# Page1.net
KiCad netlist of a schematic drawn in Altium Designer
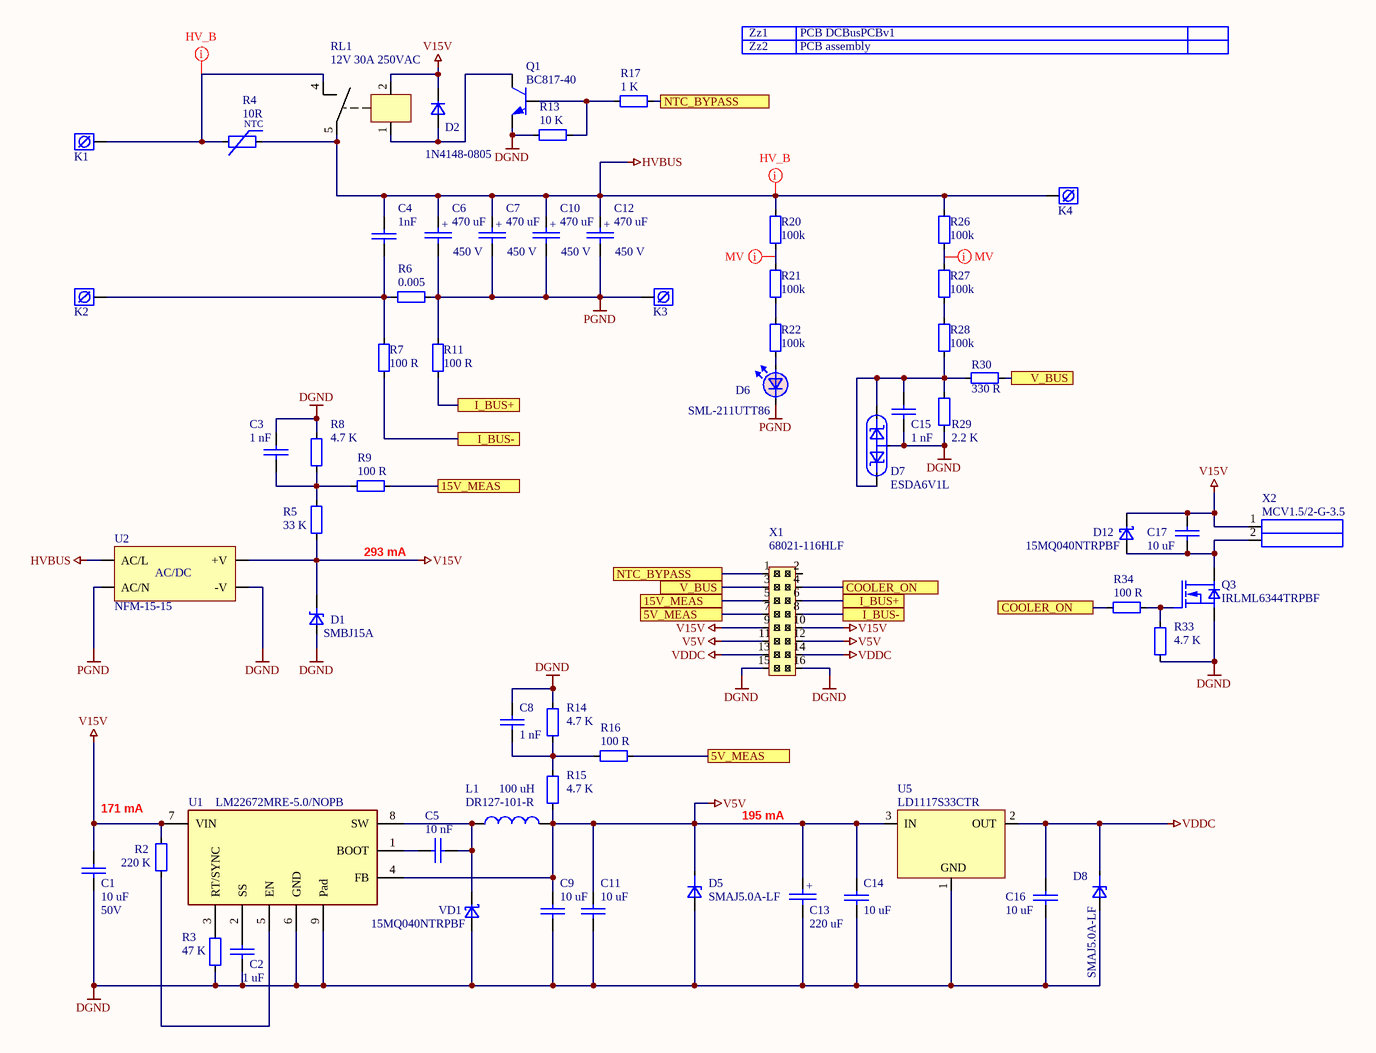
[diagram p0: Page1.SchDoc]

(export (version "E")
  (design (tool "Eeschema 10.0.6"))
  (components
    (comp (ref "C1")
      (value "10 uF")
      (footprint "3225[1210]")
      (description "10uF, 50V, 20%, Y5V (F), 1210")
      (fields
        (field (name "MANUFACTURER") "Murata Electronics North America")
        (field (name "TOLERANCE") "20%")
        (field (name "VOLTAGE") "50V")
      )
      (libsource (lib "ea_Capacitors") (part "GRM32DF51H106ZA01L"))
    )
    (comp (ref "C2")
      (value "1 uF")
      (footprint "2012[0805]")
      (description "1 uF, 10V, 10%, X7R, 0805")
      (fields (field (name "MANUFACTURER") "Murata") (field (name "TOLERANCE") "10%"))
      (libsource (lib "ea_Capacitors") (part "GRM21BR71A105KA01L"))
    )
    (comp (ref "C3")
      (value "1 nF")
      (footprint "1608[0603]")
      (description "1 nF, 50V, 10%, X7R, 0603 SMD MLC Capacitor")
      (fields (field (name "TOLERANCE") "10%") (field (name "MANUFACTURER") "SAMSUNG"))
      (libsource (lib "ea_Capacitors") (part "CVNF1.0K0603_1"))
    )
    (comp (ref "C4")
      (value "1nF")
      (footprint "B32529C8102J")
      (description "CAP FILM 1000PF 630VDC 400VAC RADIAL Lead Spacing 5mm")
      (fields (field (name "MANUFACTURER") "Epcos") (field (name "TOLERANCE") "20%"))
      (libsource (lib "ea_Capacitors") (part "B32529C8102J"))
    )
    (comp (ref "C5")
      (value "10 nF")
      (footprint "1608[0603]")
      (description "10 nF, 50V, 5%, X7R, 0603 SMD MLC Capacitor")
      (fields (field (name "TOLERANCE") "5%") (field (name "MANUFACTURER") "SAMSUNG"))
      (libsource (lib "ea_Capacitors") (part "CVNF010K0603"))
    )
    (comp (ref "C6")
      (value "470 uF")
      (footprint "ESMH451VNN471MA50T")
      (description "470uF 450V, 20%, -40..+85, 2000 Hrs @ 85°C, 35*50")
      (fields
        (field (name "MANUFACTURER") "UNITED CHEMICON")
        (field (name "TOLERANCE") "+-20%")
        (field (name "VOLTAGE") "450 V")
      )
      (libsource (lib "ea_Capacitors") (part "ESMH451VNN471MA50T"))
    )
    (comp (ref "C7")
      (value "470 uF")
      (footprint "ESMH451VNN471MA50T")
      (description "470uF 450V, 20%, -40..+85, 2000 Hrs @ 85°C, 35*50")
      (fields
        (field (name "MANUFACTURER") "UNITED CHEMICON")
        (field (name "TOLERANCE") "+-20%")
        (field (name "VOLTAGE") "450 V")
      )
      (libsource (lib "ea_Capacitors") (part "ESMH451VNN471MA50T"))
    )
    (comp (ref "C8")
      (value "1 nF")
      (footprint "1608[0603]")
      (description "1 nF, 50V, 10%, X7R, 0603 SMD MLC Capacitor")
      (fields (field (name "TOLERANCE") "10%") (field (name "MANUFACTURER") "SAMSUNG"))
      (libsource (lib "ea_Capacitors") (part "CVNF1.0K0603_1"))
    )
    (comp (ref "C9")
      (value "10 uF")
      (footprint "0805-1206")
      (description "CAP CER 10UF 10V 10% X5R 0805")
      (fields (field (name "MANUFACTURER") "Taiyo Yuden") (field (name "TOLERANCE") "10%"))
      (libsource (lib "ea_Capacitors") (part "LMK212F106ZG-T"))
    )
    (comp (ref "C10")
      (value "470 uF")
      (footprint "ESMH451VNN471MA50T")
      (description "470uF 450V, 20%, -40..+85, 2000 Hrs @ 85°C, 35*50")
      (fields
        (field (name "MANUFACTURER") "UNITED CHEMICON")
        (field (name "TOLERANCE") "+-20%")
        (field (name "VOLTAGE") "450 V")
      )
      (libsource (lib "ea_Capacitors") (part "ESMH451VNN471MA50T"))
    )
    (comp (ref "C11")
      (value "10 uF")
      (footprint "0805-1206")
      (description "CAP CER 10UF 10V 10% X5R 0805")
      (fields (field (name "MANUFACTURER") "Taiyo Yuden") (field (name "TOLERANCE") "10%"))
      (libsource (lib "ea_Capacitors") (part "LMK212F106ZG-T"))
    )
    (comp (ref "C12")
      (value "470 uF")
      (footprint "ESMH451VNN471MA50T")
      (description "470uF 450V, 20%, -40..+85, 2000 Hrs @ 85°C, 35*50")
      (fields
        (field (name "MANUFACTURER") "UNITED CHEMICON")
        (field (name "TOLERANCE") "+-20%")
        (field (name "VOLTAGE") "450 V")
      )
      (libsource (lib "ea_Capacitors") (part "ESMH451VNN471MA50T"))
    )
    (comp (ref "C13")
      (value "220 uF")
      (footprint "Tant case C (6032-28)")
      (description "220.0 uF, 10V 20%, -55...105 C, SMD Tantalum")
      (fields (field (name "MANUFACTURER") "AVX Connectors") (field (name "TOLERANCE") "20%"))
      (libsource (lib "ea_Capacitors") (part "T520C157M010ATE055"))
    )
    (comp (ref "C14")
      (value "10 uF")
      (footprint "0805-1206")
      (description "CAP CER 10UF 10V 10% X5R 0805")
      (fields (field (name "MANUFACTURER") "Taiyo Yuden") (field (name "TOLERANCE") "10%"))
      (libsource (lib "ea_Capacitors") (part "LMK212F106ZG-T"))
    )
    (comp (ref "C15")
      (value "1 nF")
      (footprint "1608[0603]")
      (description "1 nF, 50V, 10%, X7R, 0603 SMD MLC Capacitor")
      (fields (field (name "TOLERANCE") "10%") (field (name "MANUFACTURER") "SAMSUNG"))
      (libsource (lib "ea_Capacitors") (part "CVNF1.0K0603_1"))
    )
    (comp (ref "C16")
      (value "10 uF")
      (footprint "0805-1206")
      (description "CAP CER 10UF 10V 10% X5R 0805")
      (fields (field (name "MANUFACTURER") "Taiyo Yuden") (field (name "TOLERANCE") "10%"))
      (libsource (lib "ea_Capacitors") (part "LMK212F106ZG-T"))
    )
    (comp (ref "C17")
      (value "10 uF")
      (footprint "0805-1206")
      (description "CAP CER 10UF 10V 10% X5R 0805")
      (fields (field (name "MANUFACTURER") "Taiyo Yuden") (field (name "TOLERANCE") "10%"))
      (libsource (lib "ea_Capacitors") (part "LMK212F106ZG-T"))
    )
    (comp (ref "D1")
      (value "SMBJ15A")
      (footprint "SMB ST")
      (description "DIODE TVS 15V 600W UNI 5% SMD")
      (fields (field (name "MANUFACTURER") "TAIWAN SEMICONDUCTOR") (field (name "PARTNUM") "7277733RL"))
      (libsource (lib "ea_TVS_protection") (part "SMBJ15A"))
    )
    (comp (ref "D2")
      (value "1N4148-0805")
      (footprint "DIODE1206_LL4148")
      (description "Switching diode; 500mA; 4ns; 0805, 100V, 300mA")
      (fields (field (name "MANUFACTURER") "DC COMPONENTS"))
      (libsource (lib "MCHV") (part "Diode 100V 0805 1N4148"))
    )
    (comp (ref "D5")
      (value "SMAJ5.0A-LF")
      (footprint "DO-214AA_SMBJ")
      (description "TVS 400W 5.0V Unidirect")
      (fields (field (name "MANUFACTURER") "LITTELFUSE"))
      (libsource (lib "ea_TVS_protection") (part "SMAJ5.0A-LF"))
    )
    (comp (ref "D6")
      (value "SML-211UTT86")
      (footprint "0805 LED")
      (description "0805 red LED, hibright, 2 mA, 1.8V, 130°")
      (fields (field (name "MANUFACTURER") "Rohm") (field (name "PARTNUM") "511-1292-1-ND"))
      (libsource (lib "ea_Indicators") (part "SML-211UTT86"))
    )
    (comp (ref "D7")
      (value "ESDA6V1L")
      (footprint "SOT23")
      (description "Dual transil array for ESD, 6.1 V, 300 W")
      (fields (field (name "MANUFACTURER") "Micro Commercial Co") (field (name "PARTNUM") "ESDA6V1L-TPCT-ND"))
      (libsource (lib "*") (part "ESDA6V1L"))
    )
    (comp (ref "D8")
      (value "SMAJ5.0A-LF")
      (footprint "DO-214AA_SMBJ")
      (description "TVS 400W 5.0V Unidirect")
      (fields (field (name "MANUFACTURER") "LITTELFUSE"))
      (libsource (lib "ea_TVS_protection") (part "SMAJ5.0A-LF"))
    )
    (comp (ref "D12")
      (value "15MQ040NTRPBF")
      (footprint "SMA")
      (description "Schottky Power Rectifier 3A, 40V, SMA")
      (fields (field (name "MANUFACTURER") "VISHAY"))
      (libsource (lib "ea_Diodes") (part "15MQ040N"))
    )
    (comp (ref "K1")
      (value "Screw terminal KEYS7692 front")
      (footprint "KEY7692_front")
      (libsource (lib "Inverter_v2") (part "Screw terminal KEYS7692 front"))
    )
    (comp (ref "K2")
      (value "Screw terminal KEYS7692 front")
      (footprint "KEY7692_front")
      (libsource (lib "Inverter_v2") (part "Screw terminal KEYS7692 front"))
    )
    (comp (ref "K3")
      (value "Screw terminal KEYS7692 front")
      (footprint "KEY7692_front")
      (libsource (lib "Inverter_v2") (part "Screw terminal KEYS7692 front"))
    )
    (comp (ref "K4")
      (value "Screw terminal KEYS7692 front")
      (footprint "KEY7692_front")
      (libsource (lib "Inverter_v2") (part "Screw terminal KEYS7692 front"))
    )
    (comp (ref "L1")
      (value "DR127-101-R")
      (footprint "DR127")
      (description "100 uH, 1.96A, ±20%, 163 mOhm")
      (fields
        (field (name "MANUFACTURER") "Coiltronics/Div of Cooper/Bussmann")
        (field (name "PARTNUM") "513-1038-1-ND")
        (field (name "ALTIUM_VALUE") "100 uH")
      )
      (libsource (lib "ea_Inductors") (part "DR127-101-R"))
    )
    (comp (ref "Q1")
      (value "BC817-40")
      (footprint "SOT23")
      (description "NPN 45V 0,5A 0,25W B:250-600 SOT23")
      (fields (field (name "MANUFACTURER") "NXP Semiconductors") (field (name "PARTNUM") "568-1631-1-ND"))
      (libsource (lib "ea_Transistors") (part "BC817-40"))
    )
    (comp (ref "Q3")
      (value "IRLML6344TRPBF")
      (footprint "SOT23")
      (description "N-channel MOSFET, 30V, 5A, 0.030 Ohm 3.3 V, SOT-23")
      (fields
        (field (name "MANUFACTURER") "International Rectifier")
        (field (name "PARTNUM") "IRLML6344TRPBFCT-ND")
      )
      (libsource (lib "ea_MOSFET_&_drivers") (part "IRLML6344TRPBF"))
    )
    (comp (ref "R2")
      (value "220 K")
      (footprint "0603")
      (description "220 K, 1%, 0603, SMD Resistor, Taped")
      (fields (field (name "MANUFACTURER") "YAGEO AMERICA CORPORATION") (field (name "TOLERANCE") "1%"))
      (libsource (lib "ea_Resistors") (part "RL0603K220-1_1"))
    )
    (comp (ref "R3")
      (value "47 K")
      (footprint "0603")
      (description "47 K, 1%, 0603, SMD Resistor, Taped")
      (fields (field (name "MANUFACTURER") "YAGEO AMERICA CORPORATION") (field (name "TOLERANCE") "1%"))
      (libsource (lib "ea_Resistors") (part "RC0603FR-0747KL"))
    )
    (comp (ref "R4")
      (value "10R")
      (footprint "B57464")
      (description "CURRENT LIMITER INRSH 10 OHM 20%, 8A, Lead Spacing 7.5mm")
      (fields (field (name "MANUFACTURER") "EPCOS Inc") (field (name "PARTNUM") "495-4111-ND"))
      (libsource (lib "ea_Fuses") (part "B57464S100M000"))
    )
    (comp (ref "R5")
      (value "33 K")
      (footprint "0603")
      (description "33 K, 1%, 0603, SMD Resistor, Taped")
      (fields (field (name "MANUFACTURER") "YAGEO AMERICA CORPORATION") (field (name "TOLERANCE") "1%"))
      (libsource (lib "ea_Resistors") (part "RL0603K033-1_1"))
    )
    (comp (ref "R6")
      (value "0.005")
      (footprint "MCS3264")
      (description "Curr.sens.res. 0.005 OHM 2W 1% , 2512 (6432 Metric)")
      (fields (field (name "MANUFACTURER") "Ohmite") (field (name "TOLERANCE") "1%"))
      (libsource (lib "ea_Resistors") (part "MCS3264R005FER"))
    )
    (comp (ref "R7")
      (value "100 R")
      (footprint "0603")
      (description "100 R, 1%, 0603, SMD Resistor, Taped")
      (fields (field (name "MANUFACTURER") "PANASONIC") (field (name "TOLERANCE") "1%"))
      (libsource (lib "ea_Resistors") (part "RL0603E100-1_1"))
    )
    (comp (ref "R8")
      (value "4.7 K")
      (footprint "0603")
      (description "4.7 K, 1%, 0603, SMD Resistor, Taped")
      (fields (field (name "MANUFACTURER") "YAGEO AMERICA CORPORATION") (field (name "TOLERANCE") "1%"))
      (libsource (lib "ea_Resistors") (part "RL0603K004.7-1_1"))
    )
    (comp (ref "R9")
      (value "100 R")
      (footprint "0603")
      (description "100 R, 1%, 0603, SMD Resistor, Taped")
      (fields (field (name "MANUFACTURER") "PANASONIC") (field (name "TOLERANCE") "1%"))
      (libsource (lib "") (part "RL0603E100-1_1_1"))
    )
    (comp (ref "R11")
      (value "100 R")
      (footprint "0603")
      (description "100 R, 1%, 0603, SMD Resistor, Taped")
      (fields (field (name "MANUFACTURER") "PANASONIC") (field (name "TOLERANCE") "1%"))
      (libsource (lib "ea_Resistors") (part "RL0603E100-1_1"))
    )
    (comp (ref "R13")
      (value "10 K")
      (footprint "0603")
      (description "10 K, 1%, 0603, SMD Resistor, Taped")
      (fields (field (name "MANUFACTURER") "PANASONIC") (field (name "TOLERANCE") "1%"))
      (libsource (lib "ea_Resistors") (part "RL0603K010-1"))
    )
    (comp (ref "R14")
      (value "4.7 K")
      (footprint "0603")
      (description "4.7 K, 1%, 0603, SMD Resistor, Taped")
      (fields (field (name "MANUFACTURER") "YAGEO AMERICA CORPORATION") (field (name "TOLERANCE") "1%"))
      (libsource (lib "ea_Resistors") (part "RL0603K004.7-1_1"))
    )
    (comp (ref "R15")
      (value "4.7 K")
      (footprint "0603")
      (description "4.7 K, 1%, 0603, SMD Resistor, Taped")
      (fields (field (name "MANUFACTURER") "YAGEO AMERICA CORPORATION") (field (name "TOLERANCE") "1%"))
      (libsource (lib "ea_Resistors") (part "RL0603K004.7-1_1"))
    )
    (comp (ref "R16")
      (value "100 R")
      (footprint "0603")
      (description "100 R, 1%, 0603, SMD Resistor, Taped")
      (fields (field (name "MANUFACTURER") "PANASONIC") (field (name "TOLERANCE") "1%"))
      (libsource (lib "") (part "RL0603E100-1_1_1"))
    )
    (comp (ref "R17")
      (value "1 K")
      (footprint "0603")
      (description "1 K, 1%, 0603, SMD Resistor, Taped")
      (fields (field (name "MANUFACTURER") "YAGEO AMERICA CORPORATION") (field (name "TOLERANCE") "1%"))
      (libsource (lib "ea_Resistors") (part "RL0603K001-1_1"))
    )
    (comp (ref "R20")
      (value "100k")
      (footprint "3216[1206]")
      (description "100K, 1%,  1206,  200v,  SMD 1206")
      (fields (field (name "MANUFACTURER") "Panasonic") (field (name "PARTNUM") "ERJ-8ENF1003V"))
      (libsource (lib "ea_Resistors") (part "RL1206K100-1"))
    )
    (comp (ref "R21")
      (value "100k")
      (footprint "3216[1206]")
      (description "100K, 1%,  1206,  200v,  SMD 1206")
      (fields (field (name "MANUFACTURER") "Panasonic") (field (name "PARTNUM") "ERJ-8ENF1003V"))
      (libsource (lib "ea_Resistors") (part "RL1206K100-1"))
    )
    (comp (ref "R22")
      (value "100k")
      (footprint "3216[1206]")
      (description "100K, 1%,  1206,  200v,  SMD 1206")
      (fields (field (name "MANUFACTURER") "Panasonic") (field (name "PARTNUM") "ERJ-8ENF1003V"))
      (libsource (lib "ea_Resistors") (part "RL1206K100-1"))
    )
    (comp (ref "R26")
      (value "100k")
      (footprint "3216[1206]")
      (description "100K, 1%,  1206,  200v,  SMD 1206")
      (fields (field (name "MANUFACTURER") "Panasonic") (field (name "PARTNUM") "ERJ-8ENF1003V"))
      (libsource (lib "ea_Resistors") (part "RL1206K100-1"))
    )
    (comp (ref "R27")
      (value "100k")
      (footprint "3216[1206]")
      (description "100K, 1%,  1206,  200v,  SMD 1206")
      (fields (field (name "MANUFACTURER") "Panasonic") (field (name "PARTNUM") "ERJ-8ENF1003V"))
      (libsource (lib "ea_Resistors") (part "RL1206K100-1"))
    )
    (comp (ref "R28")
      (value "100k")
      (footprint "3216[1206]")
      (description "100K, 1%,  1206,  200v,  SMD 1206")
      (fields (field (name "MANUFACTURER") "Panasonic") (field (name "PARTNUM") "ERJ-8ENF1003V"))
      (libsource (lib "ea_Resistors") (part "RL1206K100-1"))
    )
    (comp (ref "R29")
      (value "2.2 K")
      (footprint "0603")
      (description "2.2 K, 1%, 0603, SMD Resistor, Taped")
      (fields (field (name "MANUFACTURER") "YAGEO AMERICA CORPORATION") (field (name "TOLERANCE") "1%"))
      (libsource (lib "ea_Resistors") (part "RL0603K002.2-1_1"))
    )
    (comp (ref "R30")
      (value "330 R")
      (footprint "0603")
      (description "330 R, 1%, 0603, SMD Resistor, Taped")
      (fields (field (name "MANUFACTURER") "YAGEO AMERICA CORPORATION") (field (name "TOLERANCE") "1%"))
      (libsource (lib "ea_Resistors") (part "RL0603E330-1_1"))
    )
    (comp (ref "R33")
      (value "4.7 K")
      (footprint "0603")
      (description "4.7 K, 1%, 0603, SMD Resistor, Taped")
      (fields (field (name "MANUFACTURER") "YAGEO AMERICA CORPORATION") (field (name "TOLERANCE") "1%"))
      (libsource (lib "ea_Resistors") (part "RL0603K004.7-1_1"))
    )
    (comp (ref "R34")
      (value "100 R")
      (footprint "0603")
      (description "100 R, 1%, 0603, SMD Resistor, Taped")
      (fields (field (name "MANUFACTURER") "PANASONIC") (field (name "TOLERANCE") "1%"))
      (libsource (lib "") (part "RL0603E100-1_1_2"))
    )
    (comp (ref "RL1")
      (value "12V 30A 250VAC")
      (footprint "T90")
      (description "Relay, SPST-NO; PCB; 144R; 9-12VDC; 30A/250VAC")
      (fields (field (name "PARTNUM") "2-1393209-8") (field (name "MANUFACTURER") "TE CONNECTIVITY"))
      (libsource (lib "MCHV") (part "Relay T9AS1D12-12"))
    )
    (comp (ref "U1")
      (value "LM22672")
      (footprint "SOIC-8 EDP")
      (description "SIMPLESWITCH, 1.0A 4.5~42VIN, 8PSOP")
      (fields
        (field (name "MANUFACTURER") "National Semiconductor")
        (field (name "PARTNUM") "LM22672MRE-5.0CT-ND")
        (field (name "PARTNAME") "LM22672MRE-5.0/NOPB")
      )
      (libsource (lib "ea_IC_Power_Reg_Ref_Sw") (part "LM22672MRE-5.0"))
    )
    (comp (ref "U2")
      (value "NFM-15-15")
      (footprint "NFM-15")
      (description "AC/DC 15W, 15V, -20..+70 C")
      (fields (field (name "MANUFACTURER") "Mean Well"))
      (libsource (lib "ea_PowerSources") (part "NFM-15-15"))
    )
    (comp (ref "U5")
      (value "LD1117S33CTR")
      (footprint "SOT-223")
      (description "Low drop positive voltage regulator, 3.3 V, 1A, SOT-223")
      (fields (field (name "MANUFACTURER") "STMicroelectronics") (field (name "PARTNUM") "497-1241-1-ND"))
      (libsource (lib "ea_IC_Power_Reg_Ref_Sw") (part "LD1117S33CTR"))
    )
    (comp (ref "VD1")
      (value "15MQ040NTRPBF")
      (footprint "SMA")
      (description "Schottky Power Rectifier 3A, 40V, SMA")
      (fields (field (name "MANUFACTURER") "VISHAY"))
      (libsource (lib "ea_Diodes") (part "15MQ040N"))
    )
    (comp (ref "X1")
      (value "68021-116HLF")
      (footprint "68021-116HLF")
      (description "Headers & Wire Housings 16P SR UNSHRD HRD .76 GOLD OVER NI")
      (fields (field (name "MANUFACTURER") "FCI") (field (name "PARTNUM") "649-68021-116HLF"))
      (libsource (lib "Inverter_v2") (part "68021-116HLF"))
    )
    (comp (ref "X2")
      (value "MCV1.5/2-G-3.5")
      (footprint "mcv1.5-2-g_3.5")
      (description "HEADER, VERTICAL, 3.5MM, 2WAY")
      (fields (field (name "MANUFACTURER") "PHOENIX CONTACT") (field (name "PARTNUM") "3704816"))
      (libsource (lib "ea_Connectors") (part "MCV1.5/2-G-3.5"))
    )
    (comp (ref "Zz1")
      (value "PCB DCBusPCBv1")
      (fields (field (name "MANUFACTURER") "Brandner") (field (name "PARTNUM") "DCBusPCBv1 board"))
      (libsource (lib "ea_Mechanical") (part "BOM item"))
    )
    (comp (ref "Zz2")
      (value "PCB assembly")
      (fields (field (name "MANUFACTURER") "ESEMDA") (field (name "PARTNUM") "DCBusPCBv2 assembly"))
      (libsource (lib "ea_Mechanical") (part "BOM item"))
    )
  )
  (nets
    (net (code "1") (name "/5V_MEAS") (class "Default")
      (node (ref "R16") (pin "2") (pinfunction "2_2") (pintype "passive"))
      (node (ref "X1") (pin "7") (pinfunction "7_7") (pintype "passive"))
    )
    (net (code "2") (name "/15V_MEAS") (class "Default")
      (node (ref "R9") (pin "2") (pinfunction "2_2") (pintype "passive"))
      (node (ref "X1") (pin "5") (pinfunction "5_5") (pintype "passive"))
    )
    (net (code "3") (name "/COOLER_ON") (class "Default")
      (node (ref "R34") (pin "2") (pinfunction "2_2") (pintype "passive"))
      (node (ref "X1") (pin "4") (pinfunction "4_4") (pintype "passive"))
    )
    (net (code "4") (name "/I_BUS+") (class "Default")
      (node (ref "R11") (pin "1") (pinfunction "1_1") (pintype "passive"))
      (node (ref "X1") (pin "6") (pinfunction "6_6") (pintype "passive"))
    )
    (net (code "5") (name "/I_BUS-") (class "Default")
      (node (ref "R7") (pin "1") (pinfunction "1_1") (pintype "passive"))
      (node (ref "X1") (pin "8") (pinfunction "8_8") (pintype "passive"))
    )
    (net (code "6") (name "/NTC_BYPASS") (class "Default")
      (node (ref "R17") (pin "1") (pinfunction "1_1") (pintype "passive"))
      (node (ref "X1") (pin "1") (pinfunction "1_1") (pintype "passive"))
    )
    (net (code "7") (name "/V_BUS") (class "Default")
      (node (ref "R30") (pin "1") (pinfunction "1_1") (pintype "passive"))
      (node (ref "X1") (pin "3") (pinfunction "3_3") (pintype "passive"))
    )
    (net (code "8") (name "DGND") (class "Default")
      (node (ref "C1") (pin "2") (pinfunction "2_2") (pintype "passive"))
      (node (ref "C11") (pin "1") (pinfunction "1_1") (pintype "passive"))
      (node (ref "C13") (pin "2") (pinfunction "2_2") (pintype "passive"))
      (node (ref "C14") (pin "1") (pinfunction "1_1") (pintype "passive"))
      (node (ref "C15") (pin "2") (pinfunction "2_2") (pintype "passive"))
      (node (ref "C16") (pin "1") (pinfunction "1_1") (pintype "passive"))
      (node (ref "C2") (pin "1") (pinfunction "1_1") (pintype "passive"))
      (node (ref "C3") (pin "1") (pinfunction "1_1") (pintype "passive"))
      (node (ref "C8") (pin "1") (pinfunction "1_1") (pintype "passive"))
      (node (ref "C9") (pin "1") (pinfunction "1_1") (pintype "passive"))
      (node (ref "D1") (pin "1") (pinfunction "1_1") (pintype "passive"))
      (node (ref "D5") (pin "2") (pinfunction "A_2") (pintype "passive"))
      (node (ref "D7") (pin "3") (pintype "passive"))
      (node (ref "D8") (pin "2") (pinfunction "A_2") (pintype "passive"))
      (node (ref "Q1") (pin "2") (pinfunction "E_2") (pintype "passive"))
      (node (ref "Q3") (pin "2") (pinfunction "S_2") (pintype "passive"))
      (node (ref "R13") (pin "1") (pinfunction "1_1") (pintype "passive"))
      (node (ref "R14") (pin "2") (pinfunction "2_2") (pintype "passive"))
      (node (ref "R29") (pin "2") (pinfunction "2_2") (pintype "passive"))
      (node (ref "R3") (pin "1") (pinfunction "1_1") (pintype "passive"))
      (node (ref "R33") (pin "1") (pinfunction "1_1") (pintype "passive"))
      (node (ref "R8") (pin "2") (pinfunction "2_2") (pintype "passive"))
      (node (ref "U1") (pin "6") (pinfunction "GND_6") (pintype "passive"))
      (node (ref "U1") (pin "9") (pinfunction "Pad_9") (pintype "passive"))
      (node (ref "U2") (pin "-V") (pinfunction "-V_-V") (pintype "passive"))
      (node (ref "U5") (pin "1") (pinfunction "GND_1") (pintype "power_in"))
      (node (ref "VD1") (pin "A") (pinfunction "A_A") (pintype "passive"))
      (node (ref "X1") (pin "15") (pinfunction "15_15") (pintype "passive"))
      (node (ref "X1") (pin "16") (pinfunction "16_16") (pintype "passive"))
    )
    (net (code "9") (name "HVBUS") (class "Default")
      (node (ref "C10") (pin "1") (pinfunction "1_1") (pintype "passive"))
      (node (ref "C12") (pin "1") (pinfunction "1_1") (pintype "passive"))
      (node (ref "C4") (pin "1") (pinfunction "1_1") (pintype "passive"))
      (node (ref "C6") (pin "1") (pinfunction "1_1") (pintype "passive"))
      (node (ref "C7") (pin "1") (pinfunction "1_1") (pintype "passive"))
      (node (ref "K4") (pin "1") (pinfunction "1_1") (pintype "passive"))
      (node (ref "R20") (pin "1") (pinfunction "1_1") (pintype "passive"))
      (node (ref "R26") (pin "1") (pinfunction "1_1") (pintype "passive"))
      (node (ref "R4") (pin "2") (pinfunction "2_2") (pintype "passive"))
      (node (ref "RL1") (pin "5") (pinfunction "5_5") (pintype "passive"))
      (node (ref "U2") (pin "AC/L") (pinfunction "AC/L_AC/L") (pintype "passive"))
    )
    (net (code "10") (name "Net-(C3-Pad2)") (class "Default")
      (node (ref "C3") (pin "2") (pinfunction "2_2") (pintype "passive"))
      (node (ref "R5") (pin "2") (pinfunction "2_2") (pintype "passive"))
      (node (ref "R8") (pin "1") (pinfunction "1_1") (pintype "passive"))
      (node (ref "R9") (pin "1") (pinfunction "1_1") (pintype "passive"))
    )
    (net (code "11") (name "Net-(C4-Pad2)") (class "Default")
      (node (ref "C4") (pin "2") (pinfunction "2_2") (pintype "passive"))
      (node (ref "K2") (pin "1") (pinfunction "1_1") (pintype "passive"))
      (node (ref "R6") (pin "1") (pinfunction "1_1") (pintype "passive"))
      (node (ref "R7") (pin "2") (pinfunction "2_2") (pintype "passive"))
    )
    (net (code "12") (name "Net-(C8-Pad2)") (class "Default")
      (node (ref "C8") (pin "2") (pinfunction "2_2") (pintype "passive"))
      (node (ref "R14") (pin "1") (pinfunction "1_1") (pintype "passive"))
      (node (ref "R15") (pin "2") (pinfunction "2_2") (pintype "passive"))
      (node (ref "R16") (pin "1") (pinfunction "1_1") (pintype "passive"))
    )
    (net (code "13") (name "Net-(C15-Pad1)") (class "Default")
      (node (ref "C15") (pin "1") (pinfunction "1_1") (pintype "passive"))
      (node (ref "D7") (pin "1") (pintype "passive"))
      (node (ref "D7") (pin "2") (pintype "passive"))
      (node (ref "R28") (pin "2") (pinfunction "2_2") (pintype "passive"))
      (node (ref "R29") (pin "1") (pinfunction "1_1") (pintype "passive"))
      (node (ref "R30") (pin "2") (pinfunction "2_2") (pintype "passive"))
    )
    (net (code "14") (name "Net-(D2-A)") (class "Default")
      (node (ref "D2") (pin "2") (pinfunction "A_2") (pintype "passive"))
      (node (ref "Q1") (pin "3") (pinfunction "C_3") (pintype "passive"))
      (node (ref "RL1") (pin "1") (pinfunction "1_1") (pintype "passive"))
    )
    (net (code "15") (name "Net-(D6-Pad1)") (class "Default")
      (node (ref "D6") (pin "1") (pinfunction "1_1") (pintype "passive"))
      (node (ref "R22") (pin "2") (pinfunction "2_2") (pintype "passive"))
    )
    (net (code "16") (name "Net-(K1-Pad1)") (class "Default")
      (node (ref "K1") (pin "1") (pinfunction "1_1") (pintype "passive"))
      (node (ref "R4") (pin "1") (pinfunction "1_1") (pintype "passive"))
      (node (ref "RL1") (pin "4") (pinfunction "4_4") (pintype "passive"))
    )
    (net (code "17") (name "Net-(Q1-B)") (class "Default")
      (node (ref "Q1") (pin "1") (pinfunction "B_1") (pintype "passive"))
      (node (ref "R13") (pin "2") (pinfunction "2_2") (pintype "passive"))
      (node (ref "R17") (pin "2") (pinfunction "2_2") (pintype "passive"))
    )
    (net (code "18") (name "Net-(Q3-D)") (class "Default")
      (node (ref "C17") (pin "1") (pinfunction "1_1") (pintype "passive"))
      (node (ref "D12") (pin "A") (pinfunction "A_A") (pintype "passive"))
      (node (ref "Q3") (pin "3") (pinfunction "D_3") (pintype "passive"))
      (node (ref "X2") (pin "2") (pinfunction "2_2") (pintype "passive"))
    )
    (net (code "19") (name "Net-(Q3-G)") (class "Default")
      (node (ref "Q3") (pin "1") (pinfunction "G_1") (pintype "passive"))
      (node (ref "R33") (pin "2") (pinfunction "2_2") (pintype "passive"))
      (node (ref "R34") (pin "1") (pinfunction "1_1") (pintype "passive"))
    )
    (net (code "20") (name "Net-(R20-Pad2)") (class "Default")
      (node (ref "R20") (pin "2") (pinfunction "2_2") (pintype "passive"))
      (node (ref "R21") (pin "1") (pinfunction "1_1") (pintype "passive"))
    )
    (net (code "21") (name "Net-(R21-Pad2)") (class "Default")
      (node (ref "R21") (pin "2") (pinfunction "2_2") (pintype "passive"))
      (node (ref "R22") (pin "1") (pinfunction "1_1") (pintype "passive"))
    )
    (net (code "22") (name "Net-(R26-Pad2)") (class "Default")
      (node (ref "R26") (pin "2") (pinfunction "2_2") (pintype "passive"))
      (node (ref "R27") (pin "1") (pinfunction "1_1") (pintype "passive"))
    )
    (net (code "23") (name "Net-(R27-Pad2)") (class "Default")
      (node (ref "R27") (pin "2") (pinfunction "2_2") (pintype "passive"))
      (node (ref "R28") (pin "1") (pinfunction "1_1") (pintype "passive"))
    )
    (net (code "24") (name "Net-(U1-BOOT)") (class "Default")
      (node (ref "C5") (pin "2") (pinfunction "2_2") (pintype "passive"))
      (node (ref "U1") (pin "1") (pinfunction "BOOT_1") (pintype "passive"))
    )
    (net (code "25") (name "Net-(U1-EN)") (class "Default")
      (node (ref "R2") (pin "1") (pinfunction "1_1") (pintype "passive"))
      (node (ref "U1") (pin "5") (pinfunction "EN_5") (pintype "passive"))
    )
    (net (code "26") (name "Net-(U1-RT{slash}SYNC)") (class "Default")
      (node (ref "R3") (pin "2") (pinfunction "2_2") (pintype "passive"))
      (node (ref "U1") (pin "3") (pinfunction "RT/SYNC_3") (pintype "passive"))
    )
    (net (code "27") (name "Net-(U1-SS)") (class "Default")
      (node (ref "C2") (pin "2") (pinfunction "2_2") (pintype "passive"))
      (node (ref "U1") (pin "2") (pinfunction "SS_2") (pintype "passive"))
    )
    (net (code "28") (name "Net-(U1-SW)") (class "Default")
      (node (ref "C5") (pin "1") (pinfunction "1_1") (pintype "passive"))
      (node (ref "L1") (pin "1") (pinfunction "1_1") (pintype "passive"))
      (node (ref "U1") (pin "8") (pinfunction "SW_8") (pintype "passive"))
      (node (ref "VD1") (pin "K") (pinfunction "K_K") (pintype "passive"))
    )
    (net (code "29") (name "PGND") (class "Default")
      (node (ref "C10") (pin "2") (pinfunction "2_2") (pintype "passive"))
      (node (ref "C12") (pin "2") (pinfunction "2_2") (pintype "passive"))
      (node (ref "C6") (pin "2") (pinfunction "2_2") (pintype "passive"))
      (node (ref "C7") (pin "2") (pinfunction "2_2") (pintype "passive"))
      (node (ref "D6") (pin "2") (pinfunction "2_2") (pintype "passive"))
      (node (ref "K3") (pin "1") (pinfunction "1_1") (pintype "passive"))
      (node (ref "R11") (pin "2") (pinfunction "2_2") (pintype "passive"))
      (node (ref "R6") (pin "2") (pinfunction "2_2") (pintype "passive"))
      (node (ref "U2") (pin "AC/N") (pinfunction "AC/N_AC/N") (pintype "passive"))
    )
    (net (code "30") (name "V5V") (class "Default")
      (node (ref "C11") (pin "2") (pinfunction "2_2") (pintype "passive"))
      (node (ref "C13") (pin "1") (pinfunction "1_1") (pintype "passive"))
      (node (ref "C14") (pin "2") (pinfunction "2_2") (pintype "passive"))
      (node (ref "C9") (pin "2") (pinfunction "2_2") (pintype "passive"))
      (node (ref "D5") (pin "1") (pinfunction "C_1") (pintype "passive"))
      (node (ref "L1") (pin "2") (pinfunction "2_2") (pintype "passive"))
      (node (ref "R15") (pin "1") (pinfunction "1_1") (pintype "passive"))
      (node (ref "U1") (pin "4") (pinfunction "FB_4") (pintype "passive"))
      (node (ref "U5") (pin "3") (pinfunction "IN_3") (pintype "power_in"))
      (node (ref "X1") (pin "11") (pinfunction "11_11") (pintype "passive"))
      (node (ref "X1") (pin "12") (pinfunction "12_12") (pintype "passive"))
    )
    (net (code "31") (name "V15V") (class "Default")
      (node (ref "C1") (pin "1") (pinfunction "1_1") (pintype "passive"))
      (node (ref "C17") (pin "2") (pinfunction "2_2") (pintype "passive"))
      (node (ref "D1") (pin "2") (pinfunction "2_2") (pintype "passive"))
      (node (ref "D12") (pin "K") (pinfunction "K_K") (pintype "passive"))
      (node (ref "D2") (pin "1") (pinfunction "C_1") (pintype "passive"))
      (node (ref "R2") (pin "2") (pinfunction "2_2") (pintype "passive"))
      (node (ref "R5") (pin "1") (pinfunction "1_1") (pintype "passive"))
      (node (ref "RL1") (pin "2") (pinfunction "2_2") (pintype "passive"))
      (node (ref "U1") (pin "7") (pinfunction "VIN_7") (pintype "passive"))
      (node (ref "U2") (pin "+V") (pinfunction "+V_+V") (pintype "passive"))
      (node (ref "X1") (pin "10") (pinfunction "10_10") (pintype "passive"))
      (node (ref "X1") (pin "9") (pinfunction "9_9") (pintype "passive"))
      (node (ref "X2") (pin "1") (pinfunction "1_1") (pintype "passive"))
    )
    (net (code "32") (name "VDDC") (class "Default")
      (node (ref "C16") (pin "2") (pinfunction "2_2") (pintype "passive"))
      (node (ref "D8") (pin "1") (pinfunction "C_1") (pintype "passive"))
      (node (ref "U5") (pin "2") (pinfunction "OUT_2") (pintype "power_in"))
      (node (ref "X1") (pin "13") (pinfunction "13_13") (pintype "passive"))
      (node (ref "X1") (pin "14") (pinfunction "14_14") (pintype "passive"))
    )
    (net (code "33") (name "unconnected-(X1-Pad2)") (class "Default")
      (node (ref "X1") (pin "2") (pinfunction "2_2") (pintype "passive"))
    )
  )
)
